# MEGA2560_Rev3e_0.net
KiCad netlist of a schematic drawn in Altium Designer
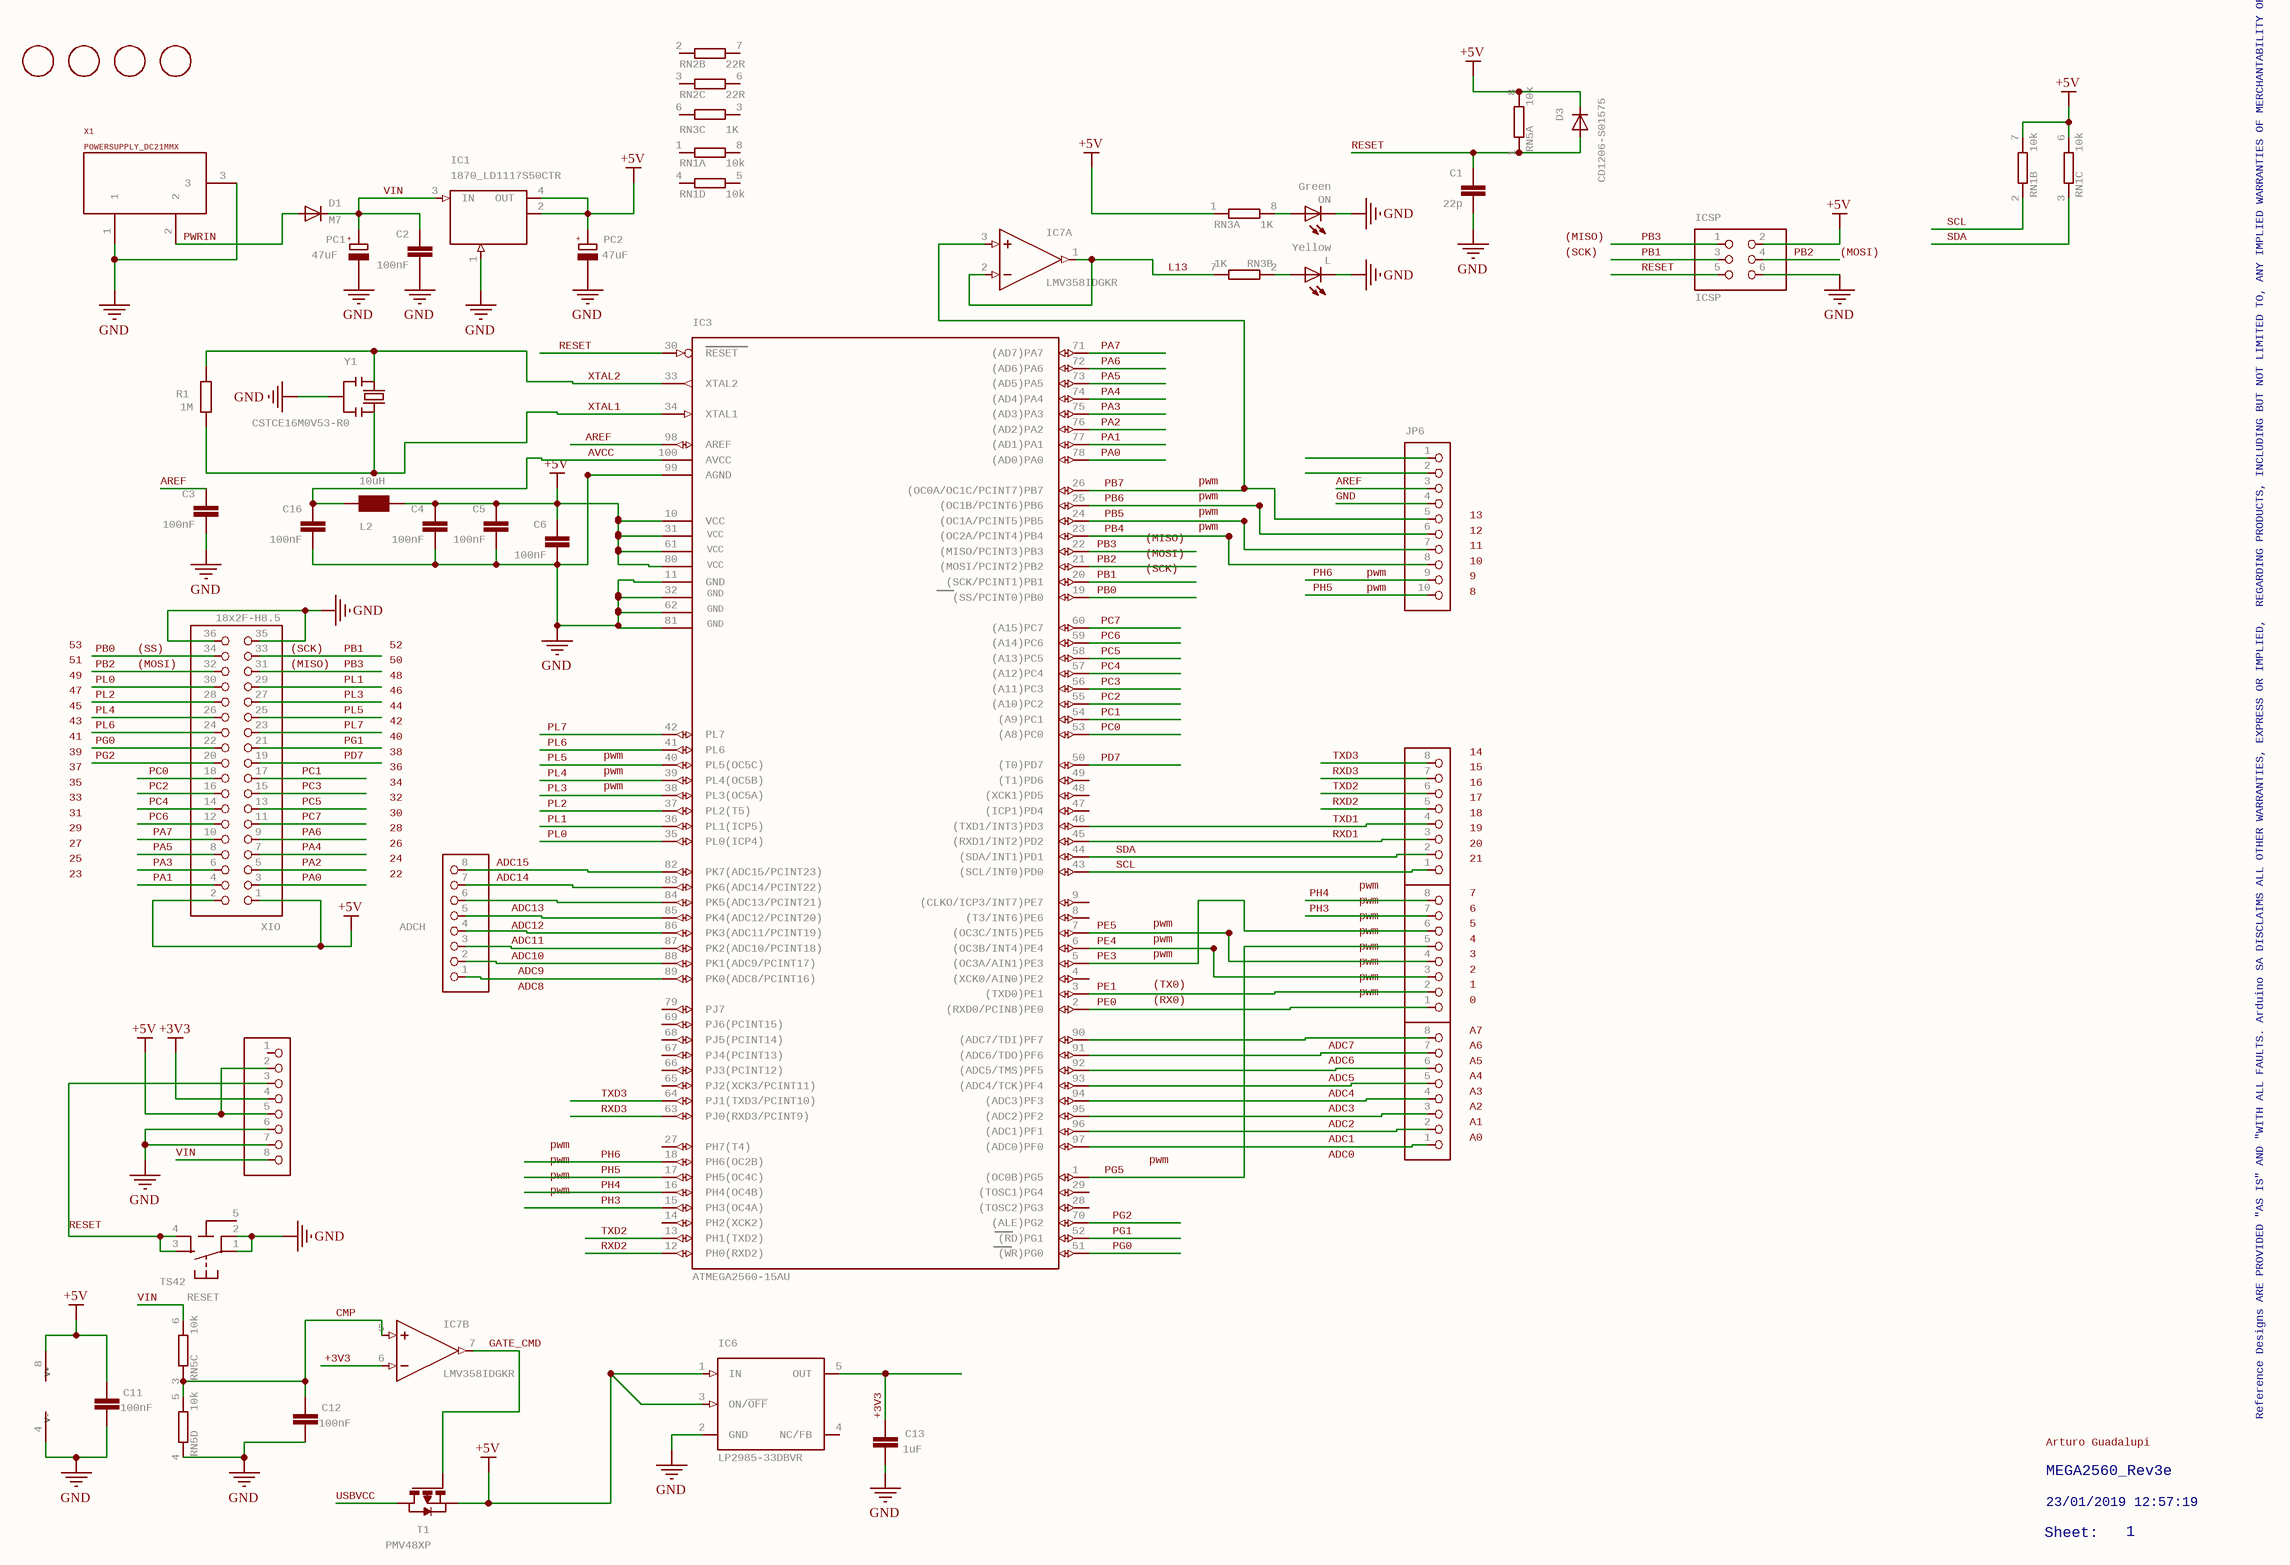
[diagram p0: MEGA2560_Rev3e_0.SchDoc]

(export (version "E")
  (design (tool "Eeschema 10.0.6"))
  (components
    (comp (ref "ADCH")
      (value "FH254-108DF08500V")
      (footprint "1X08")
      (description "Female Connector strip for Arduino bases - 8x1 F V h 8,5 p2,54mm")
      (fields (field (name "LIBRARYNAME") "Connettori"))
      (libsource (lib "Connettori") (part "0058_FH254-108DF08500V"))
    )
    (comp (ref "ADCL")
      (value "FH254-108DF08500V")
      (footprint "1X08")
      (description "Female Connector strip for Arduino bases - 8x1 F V h 8,5 p2,54mm")
      (fields (field (name "LIBRARYNAME") "Connettori"))
      (libsource (lib "Connettori") (part "0058_FH254-108DF08500V"))
    )
    (comp (ref "C1")
      (value "22p")
      (footprint "C0603-ROUND")
      (description "22pF 0603")
      (fields (field (name "PART_NUMBER") "22pF_0603"))
      (libsource (lib "Condensatori") (part "0014_22PF_0603"))
    )
    (comp (ref "C2")
      (value "100nF")
      (footprint "C0603-ROUND")
      (description "100nF 0603 50V")
      (fields (field (name "PART_NUMBER") "cl10b104kbnc"))
      (libsource (lib "Condensatori") (part "0015_100NF_0603"))
    )
    (comp (ref "C3")
      (value "100nF")
      (footprint "C0603-ROUND")
      (description "100nF 0603 50V")
      (fields (field (name "PART_NUMBER") "cl10b104kbnc"))
      (libsource (lib "Condensatori") (part "0015_100NF_0603"))
    )
    (comp (ref "C4")
      (value "100nF")
      (footprint "C0603-ROUND")
      (description "100nF 0603 50V")
      (fields (field (name "PART_NUMBER") "cl10b104kbnc"))
      (libsource (lib "Condensatori") (part "0015_100NF_0603"))
    )
    (comp (ref "C5")
      (value "100nF")
      (footprint "C0603-ROUND")
      (description "100nF 0603 50V")
      (fields (field (name "PART_NUMBER") "cl10b104kbnc"))
      (libsource (lib "Condensatori") (part "0015_100NF_0603"))
    )
    (comp (ref "C6")
      (value "100nF")
      (footprint "C0603-ROUND")
      (description "100nF 0603 50V")
      (fields (field (name "PART_NUMBER") "cl10b104kbnc"))
      (libsource (lib "Condensatori") (part "0015_100NF_0603"))
    )
    (comp (ref "C11")
      (value "100nF")
      (footprint "C0603-ROUND")
      (description "100nF 0603 50V")
      (fields (field (name "PART_NUMBER") "cl10b104kbnc"))
      (libsource (lib "") (part "0015_100NF_0603_1"))
    )
    (comp (ref "C12")
      (value "100nF")
      (footprint "C0603-ROUND")
      (description "100nF 0603 50V")
      (fields (field (name "PART_NUMBER") "cl10b104kbnc"))
      (libsource (lib "") (part "0015_100NF_0603_1"))
    )
    (comp (ref "C13")
      (value "1uF")
      (footprint "C0603-ROUND")
      (description "1uF 0603")
      (fields (field (name "PART_NUMBER") "1uF_0603/GRM188R61E105KA12D"))
      (libsource (lib "Condensatori") (part "0006_1UF_0603/GRM188R61E105KA12D"))
    )
    (comp (ref "C16")
      (value "100nF")
      (footprint "C0603-ROUND")
      (description "100nF 0603 50V")
      (fields (field (name "PART_NUMBER") "cl10b104kbnc"))
      (libsource (lib "Condensatori") (part "0015_100NF_0603"))
    )
    (comp (ref "COMMUNICATION")
      (value "FH254-108DF08500V")
      (footprint "1X08")
      (description "Female Connector strip for Arduino bases - 8x1 F V h 8,5 p2,54mm")
      (fields (field (name "LIBRARYNAME") "Connettori"))
      (libsource (lib "Connettori") (part "0058_FH254-108DF08500V"))
    )
    (comp (ref "D1")
      (value "M7")
      (footprint "SMB")
      (description "1.0A 40V SURFACE MOUNT GLASS PASSIVATED RECTIFIER   M7")
      (libsource (lib "Diodi") (part "0020_M7"))
    )
    (comp (ref "D3")
      (value "CD1206-S01575")
      (footprint "MINIMELF")
      (description "small-signal high-speed Switching Diodes   CD1206")
      (libsource (lib "Diodi") (part "0012_CD1206-S01575"))
    )
    (comp (ref "FD1")
      (value "FIDUCIALMOUNT")
      (footprint "FIDUCIA-MOUNT")
      (libsource (lib "SmartPrj") (part "FIDUCIALMOUNT"))
    )
    (comp (ref "FD2")
      (value "FIDUCIALMOUNT")
      (footprint "FIDUCIA-MOUNT")
      (libsource (lib "SmartPrj") (part "FIDUCIALMOUNT"))
    )
    (comp (ref "FD3")
      (value "FIDUCIALMOUNT")
      (footprint "FIDUCIA-MOUNT")
      (libsource (lib "SmartPrj") (part "FIDUCIALMOUNT"))
    )
    (comp (ref "FD4")
      (value "FIDUCIALMOUNT")
      (footprint "FIDUCIA-MOUNT")
      (libsource (lib "SmartPrj") (part "FIDUCIALMOUNT"))
    )
    (comp (ref "IC1")
      (value "1870_LD1117S50CTR")
      (footprint "LINEAR_SOT223")
      (description "Low-dropout linear regulator 5V  -LM1117IMPX-5.0")
      (fields (field (name "PART_NUMBER") "LD1117S50CTR"))
      (libsource (lib "IntegratedCircuits") (part "1870_LD1117S50CTR"))
    )
    (comp (ref "IC3")
      (value "ATMEGA2560-15AU")
      (footprint "TQFP100")
      (description "8-bit Microcontroller with 256K Bytes In-System Programmable Flash - ATMEGA2560-16AU")
      (fields
        (field (name "GND") "GND")
        (field (name "GND_1") "GND")
        (field (name "GND_2") "GND")
        (field (name "VCC") "VCC")
        (field (name "VCC_1") "VCC")
        (field (name "VCC_2") "VCC")
        (field (name "PART_NUMBER") "ATMEGA2560-16AU")
      )
      (libsource (lib "IntegratedCircuits") (part "0023_ATMEGA2560-16AU"))
    )
    (comp (ref "IC6")
      (value "LP2985-33DBVR")
      (footprint "SOT23-DBV")
      (description "150-mA LOW-NOISE LOW-DROPOUT REGULATOR WITH SHUTDOWN   LP2985-33DBVR")
      (fields (field (name "PART_NUMBER") "TEXLP2985-33DBVR"))
      (libsource (lib "IntegratedCircuits") (part "0008_TEXLP2985-33DBVR"))
    )
    (comp (ref "IC7")
      (value "LMV358IDGKR")
      (footprint "MSOP08")
      (fields (field (name "V+") "V+") (field (name "V-") "V-"))
      (libsource (lib "IntegratedCircuits") (part "0021_LMV358IDGKR"))
    )
    (comp (ref "ICSP")
      (value "ICSP")
      (footprint "2X03")
      (description "3x2 M V h 8,5 mm p2,54")
      (fields (field (name "PART_NUMBER") "PH254-203DF118A00V") (field (name "LIBRARYNAME") "Connettori"))
      (libsource (lib "Connettori") (part "0114_PH254-203DF118A00V"))
    )
    (comp (ref "JP6")
      (value "FH254-110DF08500V")
      (footprint "1X10")
      (description "Female Connector strip for Arduino bases - 10x1 F V h 8,5 p2,54 serigrafato STRISCIA VUOTA")
      (fields (field (name "PART_NUMBER") "FH254-110DF08500T30") (field (name "LIBRARYNAME") "Connettori"))
      (libsource (lib "Connettori") (part "1216_FH254-110DF08500T30"))
    )
    (comp (ref "L")
      (value "Yellow")
      (footprint "CHIPLED_0805")
      (description "LED YELLOW - SMD - 0805")
      (fields (field (name "PART_NUMBER") "KPT-2012YC"))
      (libsource (lib "Opto") (part "0044_KPT-2012YC"))
    )
    (comp (ref "L2")
      (value "10uH")
      (footprint "0805")
      (description "10uH 0805")
      (fields (field (name "PART_NUMBER") "CV201210-100K"))
      (libsource (lib "Induttanze") (part "0715_CV201210-100K"))
    )
    (comp (ref "ON")
      (value "Green")
      (footprint "CHIPLED_0805")
      (description "LED GREEN - SMD-0805")
      (fields (field (name "PART_NUMBER") "KPT-2012SGC"))
      (libsource (lib "Opto") (part "0043_KPT-2012SGC"))
    )
    (comp (ref "PC1")
      (value "47uF")
      (footprint "PANASONIC_D")
      (fields (field (name "+") "+"))
      (libsource (lib "Condensatori") (part "0113_47UF"))
    )
    (comp (ref "PC2")
      (value "47uF")
      (footprint "PANASONIC_D")
      (fields (field (name "+") "+"))
      (libsource (lib "Condensatori") (part "0113_47UF"))
    )
    (comp (ref "POWER")
      (value "FH254-108DF08500V")
      (footprint "1X08")
      (description "Female Connector strip for Arduino bases - 8x1 F V h 8,5 p2,54 serigrafato POWER")
      (fields (field (name "PART_NUMBER") "FH254-108DF08500T21") (field (name "LIBRARYNAME") "Connettori"))
      (libsource (lib "Connettori") (part "1217_FH254-108DF08500T21"))
    )
    (comp (ref "PWML")
      (value "FH254-108DF08500V")
      (footprint "1X08")
      (description "Female Connector strip for Arduino bases - 8x1 F V h 8,5 p2,54 serigrafato DIGITAL")
      (fields (field (name "PART_NUMBER") "FH254-108DF08500T20") (field (name "LIBRARYNAME") "Connettori"))
      (libsource (lib "Connettori") (part "1218_FH254-108DF08500T20"))
    )
    (comp (ref "R1")
      (value "1M")
      (footprint "R0603-ROUND")
      (description "1M 0603")
      (fields (field (name "PART_NUMBER") "0603_1M") (field (name "LIBRARYNAME") "Resistenze"))
      (libsource (lib "Resistenze") (part "0004_0603_1M"))
    )
    (comp (ref "RESET")
      (value "TS42")
      (footprint "TS42")
      (description "Pushbutton 6x6 Smd - White")
      (fields (field (name "PART_NUMBER") "IT-1157AHNP-160G-G_GTR"))
      (libsource (lib "Switches") (part "0946_TS42031-160W-TR-7260"))
    )
    (comp (ref "RN1")
      (value "10k")
      (footprint "CAY16")
      (description "10K 064 R")
      (fields
        (field (name "PART_NUMBER") "064R_10K_/_CAY16-103J4LF")
        (field (name "LIBRARYNAME") "Resistenze")
      )
      (libsource (lib "Resistenze") (part "0016_064R_10K_/_CAY16-103J4LF"))
    )
    (comp (ref "RN2")
      (value "22R")
      (footprint "CAY16")
      (description "22R 064R")
      (fields
        (field (name "PART_NUMBER") "064R_22R_/_CAY16-220J4LF")
        (field (name "LIBRARYNAME") "Resistenze")
      )
      (libsource (lib "Resistenze") (part "0003_064R_22R_/_CAY16-220J4LF"))
    )
    (comp (ref "RN3")
      (value "1K")
      (footprint "CAY16")
      (description "1K 064R")
      (fields
        (field (name "PART_NUMBER") "064R_1K_/_CAY16-102J4LF")
        (field (name "LIBRARYNAME") "Resistenze")
      )
      (libsource (lib "Resistenze") (part "0005_064R_1K_/_CAY16-102J4LF"))
    )
    (comp (ref "RN5")
      (value "10k")
      (footprint "CAY16")
      (description "10K 064 R")
      (fields
        (field (name "PART_NUMBER") "064R_10K_/_CAY16-103J4LF")
        (field (name "LIBRARYNAME") "Resistenze")
      )
      (libsource (lib "Resistenze") (part "0016_064R_10K_/_CAY16-103J4LF"))
    )
    (comp (ref "T1")
      (value "PMV48XP")
      (footprint "SOT-23")
      (description "20 V, 3.5 A P-channel Trench MOSFET - PMV48XP")
      (libsource (lib "Transistors") (part "0297_PMV48XP"))
    )
    (comp (ref "X1")
      (value "POWERSUPPLY_DC21MMX")
      (footprint "POWERSUPPLY_DC-21MM")
      (libsource (lib "SmartPrj") (part "POWERSUPPLY_DC21MMX"))
    )
    (comp (ref "XIO")
      (value "18x2F-H8.5")
      (footprint "2X18")
      (description "18x2 F V h 8,5 p2,54")
      (fields (field (name "PART_NUMBER") "FH254-218DF08500V") (field (name "LIBRARYNAME") "Connettori"))
      (libsource (lib "Connettori") (part "0060_FH254-218DF08500V"))
    )
    (comp (ref "Y1")
      (value "CSTCE16M0V53-R0")
      (footprint "RESONATOR")
      (description "16Mhz - SMD")
      (fields (field (name "LIBRARYNAME") "Cristalli"))
      (libsource (lib "Cristalli") (part "0011_CSTCE16M0V53-R0"))
    )
  )
  (nets
    (net (code "1") (name "+3V3") (class "Default")
      (node (ref "C13") (pin "2") (pinfunction "2_2") (pintype "passive"))
      (node (ref "IC6") (pin "5") (pinfunction "OUT_5") (pintype "passive"))
      (node (ref "IC7") (pin "6") (pinfunction "-IN_6") (pintype "input"))
      (node (ref "POWER") (pin "4") (pinfunction "4_4") (pintype "passive"))
    )
    (net (code "2") (name "+5V") (class "Default")
      (node (ref "C11") (pin "2") (pinfunction "2_2") (pintype "passive"))
      (node (ref "C4") (pin "1") (pinfunction "1_1") (pintype "passive"))
      (node (ref "C5") (pin "1") (pinfunction "1_1") (pintype "passive"))
      (node (ref "C6") (pin "1") (pinfunction "1_1") (pintype "passive"))
      (node (ref "D3") (pin "C") (pinfunction "C_C") (pintype "passive"))
      (node (ref "IC1") (pin "2") (pinfunction "OUT_2") (pintype "passive"))
      (node (ref "IC1") (pin "4") (pinfunction "OUT_4") (pintype "passive"))
      (node (ref "IC3") (pin "10") (pinfunction "VCC_10") (pintype "power_in"))
      (node (ref "IC3") (pin "31") (pinfunction "VCC1_31") (pintype "power_in"))
      (node (ref "IC3") (pin "61") (pinfunction "VCC2_61") (pintype "power_in"))
      (node (ref "IC3") (pin "80") (pinfunction "VCC3_80") (pintype "power_in"))
      (node (ref "IC6") (pin "1") (pinfunction "IN_1") (pintype "input"))
      (node (ref "IC6") (pin "3") (pinfunction "ON/~{OFF}_3") (pintype "input"))
      (node (ref "IC7") (pin "8") (pinfunction "V+_8") (pintype "power_in"))
      (node (ref "ICSP") (pin "2") (pinfunction "2_2") (pintype "passive"))
      (node (ref "L2") (pin "2") (pinfunction "2_2") (pintype "passive"))
      (node (ref "PC2") (pin "+") (pinfunction "+_+") (pintype "passive"))
      (node (ref "POWER") (pin "2") (pinfunction "2_2") (pintype "passive"))
      (node (ref "POWER") (pin "5") (pinfunction "5_5") (pintype "passive"))
      (node (ref "RN1") (pin "6") (pinfunction "2_6") (pintype "passive"))
      (node (ref "RN1") (pin "7") (pinfunction "2_7") (pintype "passive"))
      (node (ref "RN3") (pin "1") (pinfunction "1_1") (pintype "passive"))
      (node (ref "RN5") (pin "8") (pinfunction "2_8") (pintype "passive"))
      (node (ref "T1") (pin "2") (pinfunction "S_2") (pintype "passive"))
      (node (ref "XIO") (pin "1") (pinfunction "1_1") (pintype "passive"))
      (node (ref "XIO") (pin "2") (pinfunction "2_2") (pintype "passive"))
    )
    (net (code "3") (name "/ADC0") (class "Default")
      (node (ref "ADCL") (pin "1") (pinfunction "1_1") (pintype "passive"))
      (node (ref "IC3") (pin "97") (pinfunction "(ADC0)PF0_97") (pintype "bidirectional"))
    )
    (net (code "4") (name "/ADC1") (class "Default")
      (node (ref "ADCL") (pin "2") (pinfunction "2_2") (pintype "passive"))
      (node (ref "IC3") (pin "96") (pinfunction "(ADC1)PF1_96") (pintype "bidirectional"))
    )
    (net (code "5") (name "/ADC2") (class "Default")
      (node (ref "ADCL") (pin "3") (pinfunction "3_3") (pintype "passive"))
      (node (ref "IC3") (pin "95") (pinfunction "(ADC2)PF2_95") (pintype "bidirectional"))
    )
    (net (code "6") (name "/ADC3") (class "Default")
      (node (ref "ADCL") (pin "4") (pinfunction "4_4") (pintype "passive"))
      (node (ref "IC3") (pin "94") (pinfunction "(ADC3)PF3_94") (pintype "bidirectional"))
    )
    (net (code "7") (name "/ADC4") (class "Default")
      (node (ref "ADCL") (pin "5") (pinfunction "5_5") (pintype "passive"))
      (node (ref "IC3") (pin "93") (pinfunction "(ADC4/TCK)PF4_93") (pintype "bidirectional"))
    )
    (net (code "8") (name "/ADC5") (class "Default")
      (node (ref "ADCL") (pin "6") (pinfunction "6_6") (pintype "passive"))
      (node (ref "IC3") (pin "92") (pinfunction "(ADC5/TMS)PF5_92") (pintype "bidirectional"))
    )
    (net (code "9") (name "/ADC6") (class "Default")
      (node (ref "ADCL") (pin "7") (pinfunction "7_7") (pintype "passive"))
      (node (ref "IC3") (pin "91") (pinfunction "(ADC6/TDO)PF6_91") (pintype "bidirectional"))
    )
    (net (code "10") (name "/ADC7") (class "Default")
      (node (ref "ADCL") (pin "8") (pinfunction "8_8") (pintype "passive"))
      (node (ref "IC3") (pin "90") (pinfunction "(ADC7/TDI)PF7_90") (pintype "bidirectional"))
    )
    (net (code "11") (name "/ADC8") (class "Default")
      (node (ref "ADCH") (pin "1") (pinfunction "1_1") (pintype "passive"))
      (node (ref "IC3") (pin "89") (pinfunction "PK0(ADC8/PCINT16)_89") (pintype "bidirectional"))
    )
    (net (code "12") (name "/ADC9") (class "Default")
      (node (ref "ADCH") (pin "2") (pinfunction "2_2") (pintype "passive"))
      (node (ref "IC3") (pin "88") (pinfunction "PK1(ADC9/PCINT17)_88") (pintype "bidirectional"))
    )
    (net (code "13") (name "/ADC10") (class "Default")
      (node (ref "ADCH") (pin "3") (pinfunction "3_3") (pintype "passive"))
      (node (ref "IC3") (pin "87") (pinfunction "PK2(ADC10/PCINT18)_87") (pintype "bidirectional"))
    )
    (net (code "14") (name "/ADC11") (class "Default")
      (node (ref "ADCH") (pin "4") (pinfunction "4_4") (pintype "passive"))
      (node (ref "IC3") (pin "86") (pinfunction "PK3(ADC11/PCINT19)_86") (pintype "bidirectional"))
    )
    (net (code "15") (name "/ADC12") (class "Default")
      (node (ref "ADCH") (pin "5") (pinfunction "5_5") (pintype "passive"))
      (node (ref "IC3") (pin "85") (pinfunction "PK4(ADC12/PCINT20)_85") (pintype "bidirectional"))
    )
    (net (code "16") (name "/ADC13") (class "Default")
      (node (ref "ADCH") (pin "6") (pinfunction "6_6") (pintype "passive"))
      (node (ref "IC3") (pin "84") (pinfunction "PK5(ADC13/PCINT21)_84") (pintype "bidirectional"))
    )
    (net (code "17") (name "/ADC14") (class "Default")
      (node (ref "ADCH") (pin "7") (pinfunction "7_7") (pintype "passive"))
      (node (ref "IC3") (pin "83") (pinfunction "PK6(ADC14/PCINT22)_83") (pintype "bidirectional"))
    )
    (net (code "18") (name "/ADC15") (class "Default")
      (node (ref "ADCH") (pin "8") (pinfunction "8_8") (pintype "passive"))
      (node (ref "IC3") (pin "82") (pinfunction "PK7(ADC15/PCINT23)_82") (pintype "bidirectional"))
    )
    (net (code "19") (name "/AREF") (class "Default")
      (node (ref "C3") (pin "1") (pinfunction "1_1") (pintype "passive"))
      (node (ref "IC3") (pin "98") (pinfunction "AREF_98") (pintype "bidirectional"))
      (node (ref "JP6") (pin "3") (pinfunction "3_3") (pintype "passive"))
    )
    (net (code "20") (name "/AVCC") (class "Default")
      (node (ref "C16") (pin "1") (pinfunction "1_1") (pintype "passive"))
      (node (ref "IC3") (pin "100") (pinfunction "AVCC_100") (pintype "power_in"))
      (node (ref "L2") (pin "1") (pinfunction "1_1") (pintype "passive"))
    )
    (net (code "21") (name "/CMP") (class "Default")
      (node (ref "C12") (pin "2") (pinfunction "2_2") (pintype "passive"))
      (node (ref "IC7") (pin "5") (pinfunction "+IN_5") (pintype "input"))
      (node (ref "RN5") (pin "3") (pinfunction "1_3") (pintype "passive"))
      (node (ref "RN5") (pin "5") (pinfunction "2_5") (pintype "passive"))
    )
    (net (code "22") (name "/GATE_CMD") (class "Default")
      (node (ref "IC7") (pin "7") (pinfunction "OUT_7") (pintype "output"))
      (node (ref "T1") (pin "3") (pinfunction "G_3") (pintype "passive"))
    )
    (net (code "23") (name "/L13") (class "Default")
      (node (ref "IC7") (pin "1") (pinfunction "OUT_1") (pintype "output"))
      (node (ref "IC7") (pin "2") (pinfunction "-IN_2") (pintype "input"))
      (node (ref "RN3") (pin "7") (pinfunction "2_7") (pintype "passive"))
    )
    (net (code "24") (name "/PA0") (class "Default")
      (node (ref "IC3") (pin "78") (pinfunction "(AD0)PA0_78") (pintype "bidirectional"))
      (node (ref "XIO") (pin "3") (pinfunction "3_3") (pintype "passive"))
    )
    (net (code "25") (name "/PA1") (class "Default")
      (node (ref "IC3") (pin "77") (pinfunction "(AD1)PA1_77") (pintype "bidirectional"))
      (node (ref "XIO") (pin "4") (pinfunction "4_4") (pintype "passive"))
    )
    (net (code "26") (name "/PA2") (class "Default")
      (node (ref "IC3") (pin "76") (pinfunction "(AD2)PA2_76") (pintype "bidirectional"))
      (node (ref "XIO") (pin "5") (pinfunction "5_5") (pintype "passive"))
    )
    (net (code "27") (name "/PA3") (class "Default")
      (node (ref "IC3") (pin "75") (pinfunction "(AD3)PA3_75") (pintype "bidirectional"))
      (node (ref "XIO") (pin "6") (pinfunction "6_6") (pintype "passive"))
    )
    (net (code "28") (name "/PA4") (class "Default")
      (node (ref "IC3") (pin "74") (pinfunction "(AD4)PA4_74") (pintype "bidirectional"))
      (node (ref "XIO") (pin "7") (pinfunction "7_7") (pintype "passive"))
    )
    (net (code "29") (name "/PA5") (class "Default")
      (node (ref "IC3") (pin "73") (pinfunction "(AD5)PA5_73") (pintype "bidirectional"))
      (node (ref "XIO") (pin "8") (pinfunction "8_8") (pintype "passive"))
    )
    (net (code "30") (name "/PA6") (class "Default")
      (node (ref "IC3") (pin "72") (pinfunction "(AD6)PA6_72") (pintype "bidirectional"))
      (node (ref "XIO") (pin "9") (pinfunction "9_9") (pintype "passive"))
    )
    (net (code "31") (name "/PA7") (class "Default")
      (node (ref "IC3") (pin "71") (pinfunction "(AD7)PA7_71") (pintype "bidirectional"))
      (node (ref "XIO") (pin "10") (pinfunction "10_10") (pintype "passive"))
    )
    (net (code "32") (name "/PB0") (class "Default")
      (node (ref "IC3") (pin "19") (pinfunction "(SS/PCINT0)PB0_19") (pintype "bidirectional"))
      (node (ref "XIO") (pin "34") (pinfunction "34_34") (pintype "passive"))
    )
    (net (code "33") (name "/PB1") (class "Default")
      (node (ref "IC3") (pin "20") (pinfunction "(SCK/PCINT1)PB1_20") (pintype "bidirectional"))
      (node (ref "ICSP") (pin "3") (pinfunction "3_3") (pintype "passive"))
      (node (ref "XIO") (pin "33") (pinfunction "33_33") (pintype "passive"))
    )
    (net (code "34") (name "/PB2") (class "Default")
      (node (ref "IC3") (pin "21") (pinfunction "(MOSI/PCINT2)PB2_21") (pintype "bidirectional"))
      (node (ref "ICSP") (pin "4") (pinfunction "4_4") (pintype "passive"))
      (node (ref "XIO") (pin "32") (pinfunction "32_32") (pintype "passive"))
    )
    (net (code "35") (name "/PB3") (class "Default")
      (node (ref "IC3") (pin "22") (pinfunction "(MISO/PCINT3)PB3_22") (pintype "bidirectional"))
      (node (ref "ICSP") (pin "1") (pinfunction "1_1") (pintype "passive"))
      (node (ref "XIO") (pin "31") (pinfunction "31_31") (pintype "passive"))
    )
    (net (code "36") (name "/PB4") (class "Default")
      (node (ref "IC3") (pin "23") (pinfunction "(OC2A/PCINT4)PB4_23") (pintype "bidirectional"))
      (node (ref "JP6") (pin "8") (pinfunction "8_8") (pintype "passive"))
    )
    (net (code "37") (name "/PB5") (class "Default")
      (node (ref "IC3") (pin "24") (pinfunction "(OC1A/PCINT5)PB5_24") (pintype "bidirectional"))
      (node (ref "JP6") (pin "7") (pinfunction "7_7") (pintype "passive"))
    )
    (net (code "38") (name "/PB6") (class "Default")
      (node (ref "IC3") (pin "25") (pinfunction "(OC1B/PCINT6)PB6_25") (pintype "bidirectional"))
      (node (ref "JP6") (pin "6") (pinfunction "6_6") (pintype "passive"))
    )
    (net (code "39") (name "/PB7") (class "Default")
      (node (ref "IC3") (pin "26") (pinfunction "(OC0A/OC1C/PCINT7)PB7_26") (pintype "bidirectional"))
      (node (ref "IC7") (pin "3") (pinfunction "+IN_3") (pintype "input"))
      (node (ref "JP6") (pin "5") (pinfunction "5_5") (pintype "passive"))
    )
    (net (code "40") (name "/PC0") (class "Default")
      (node (ref "IC3") (pin "53") (pinfunction "(A8)PC0_53") (pintype "bidirectional"))
      (node (ref "XIO") (pin "18") (pinfunction "18_18") (pintype "passive"))
    )
    (net (code "41") (name "/PC1") (class "Default")
      (node (ref "IC3") (pin "54") (pinfunction "(A9)PC1_54") (pintype "bidirectional"))
      (node (ref "XIO") (pin "17") (pinfunction "17_17") (pintype "passive"))
    )
    (net (code "42") (name "/PC2") (class "Default")
      (node (ref "IC3") (pin "55") (pinfunction "(A10)PC2_55") (pintype "bidirectional"))
      (node (ref "XIO") (pin "16") (pinfunction "16_16") (pintype "passive"))
    )
    (net (code "43") (name "/PC3") (class "Default")
      (node (ref "IC3") (pin "56") (pinfunction "(A11)PC3_56") (pintype "bidirectional"))
      (node (ref "XIO") (pin "15") (pinfunction "15_15") (pintype "passive"))
    )
    (net (code "44") (name "/PC4") (class "Default")
      (node (ref "IC3") (pin "57") (pinfunction "(A12)PC4_57") (pintype "bidirectional"))
      (node (ref "XIO") (pin "14") (pinfunction "14_14") (pintype "passive"))
    )
    (net (code "45") (name "/PC5") (class "Default")
      (node (ref "IC3") (pin "58") (pinfunction "(A13)PC5_58") (pintype "bidirectional"))
      (node (ref "XIO") (pin "13") (pinfunction "13_13") (pintype "passive"))
    )
    (net (code "46") (name "/PC6") (class "Default")
      (node (ref "IC3") (pin "59") (pinfunction "(A14)PC6_59") (pintype "bidirectional"))
      (node (ref "XIO") (pin "12") (pinfunction "12_12") (pintype "passive"))
    )
    (net (code "47") (name "/PC7") (class "Default")
      (node (ref "IC3") (pin "60") (pinfunction "(A15)PC7_60") (pintype "bidirectional"))
      (node (ref "XIO") (pin "11") (pinfunction "11_11") (pintype "passive"))
    )
    (net (code "48") (name "/PD7") (class "Default")
      (node (ref "IC3") (pin "50") (pinfunction "(T0)PD7_50") (pintype "bidirectional"))
      (node (ref "XIO") (pin "19") (pinfunction "19_19") (pintype "passive"))
    )
    (net (code "49") (name "/PE0") (class "Default")
      (node (ref "IC3") (pin "2") (pinfunction "(RXD0/PCIN8)PE0_2") (pintype "bidirectional"))
      (node (ref "PWML") (pin "1") (pinfunction "1_1") (pintype "passive"))
    )
    (net (code "50") (name "/PE1") (class "Default")
      (node (ref "IC3") (pin "3") (pinfunction "(TXD0)PE1_3") (pintype "bidirectional"))
      (node (ref "PWML") (pin "2") (pinfunction "2_2") (pintype "passive"))
    )
    (net (code "51") (name "/PE3") (class "Default")
      (node (ref "IC3") (pin "5") (pinfunction "(OC3A/AIN1)PE3_5") (pintype "bidirectional"))
      (node (ref "PWML") (pin "6") (pinfunction "6_6") (pintype "passive"))
    )
    (net (code "52") (name "/PE4") (class "Default")
      (node (ref "IC3") (pin "6") (pinfunction "(OC3B/INT4)PE4_6") (pintype "bidirectional"))
      (node (ref "PWML") (pin "3") (pinfunction "3_3") (pintype "passive"))
    )
    (net (code "53") (name "/PE5") (class "Default")
      (node (ref "IC3") (pin "7") (pinfunction "(OC3C/INT5)PE5_7") (pintype "bidirectional"))
      (node (ref "PWML") (pin "4") (pinfunction "4_4") (pintype "passive"))
    )
    (net (code "54") (name "/PG0") (class "Default")
      (node (ref "IC3") (pin "51") (pinfunction "(WR)PG0_51") (pintype "bidirectional"))
      (node (ref "XIO") (pin "22") (pinfunction "22_22") (pintype "passive"))
    )
    (net (code "55") (name "/PG1") (class "Default")
      (node (ref "IC3") (pin "52") (pinfunction "(RD)PG1_52") (pintype "bidirectional"))
      (node (ref "XIO") (pin "21") (pinfunction "21_21") (pintype "passive"))
    )
    (net (code "56") (name "/PG2") (class "Default")
      (node (ref "IC3") (pin "70") (pinfunction "(ALE)PG2_70") (pintype "bidirectional"))
      (node (ref "XIO") (pin "20") (pinfunction "20_20") (pintype "passive"))
    )
    (net (code "57") (name "/PG5") (class "Default")
      (node (ref "IC3") (pin "1") (pinfunction "(OC0B)PG5_1") (pintype "bidirectional"))
      (node (ref "PWML") (pin "5") (pinfunction "5_5") (pintype "passive"))
    )
    (net (code "58") (name "/PH3") (class "Default")
      (node (ref "IC3") (pin "15") (pinfunction "PH3(OC4A)_15") (pintype "bidirectional"))
      (node (ref "PWML") (pin "7") (pinfunction "7_7") (pintype "passive"))
    )
    (net (code "59") (name "/PH4") (class "Default")
      (node (ref "IC3") (pin "16") (pinfunction "PH4(OC4B)_16") (pintype "bidirectional"))
      (node (ref "PWML") (pin "8") (pinfunction "8_8") (pintype "passive"))
    )
    (net (code "60") (name "/PH5") (class "Default")
      (node (ref "IC3") (pin "17") (pinfunction "PH5(OC4C)_17") (pintype "bidirectional"))
      (node (ref "JP6") (pin "10") (pinfunction "10_10") (pintype "passive"))
    )
    (net (code "61") (name "/PH6") (class "Default")
      (node (ref "IC3") (pin "18") (pinfunction "PH6(OC2B)_18") (pintype "bidirectional"))
      (node (ref "JP6") (pin "9") (pinfunction "9_9") (pintype "passive"))
    )
    (net (code "62") (name "/PL0") (class "Default")
      (node (ref "IC3") (pin "35") (pinfunction "PL0(ICP4)_35") (pintype "bidirectional"))
      (node (ref "XIO") (pin "30") (pinfunction "30_30") (pintype "passive"))
    )
    (net (code "63") (name "/PL1") (class "Default")
      (node (ref "IC3") (pin "36") (pinfunction "PL1(ICP5)_36") (pintype "bidirectional"))
      (node (ref "XIO") (pin "29") (pinfunction "29_29") (pintype "passive"))
    )
    (net (code "64") (name "/PL2") (class "Default")
      (node (ref "IC3") (pin "37") (pinfunction "PL2(T5)_37") (pintype "bidirectional"))
      (node (ref "XIO") (pin "28") (pinfunction "28_28") (pintype "passive"))
    )
    (net (code "65") (name "/PL3") (class "Default")
      (node (ref "IC3") (pin "38") (pinfunction "PL3(OC5A)_38") (pintype "bidirectional"))
      (node (ref "XIO") (pin "27") (pinfunction "27_27") (pintype "passive"))
    )
    (net (code "66") (name "/PL4") (class "Default")
      (node (ref "IC3") (pin "39") (pinfunction "PL4(OC5B)_39") (pintype "bidirectional"))
      (node (ref "XIO") (pin "26") (pinfunction "26_26") (pintype "passive"))
    )
    (net (code "67") (name "/PL5") (class "Default")
      (node (ref "IC3") (pin "40") (pinfunction "PL5(OC5C)_40") (pintype "bidirectional"))
      (node (ref "XIO") (pin "25") (pinfunction "25_25") (pintype "passive"))
    )
    (net (code "68") (name "/PL6") (class "Default")
      (node (ref "IC3") (pin "41") (pinfunction "PL6_41") (pintype "bidirectional"))
      (node (ref "XIO") (pin "24") (pinfunction "24_24") (pintype "passive"))
    )
    (net (code "69") (name "/PL7") (class "Default")
      (node (ref "IC3") (pin "42") (pinfunction "PL7_42") (pintype "bidirectional"))
      (node (ref "XIO") (pin "23") (pinfunction "23_23") (pintype "passive"))
    )
    (net (code "70") (name "/PWRIN") (class "Default")
      (node (ref "D1") (pin "A") (pinfunction "A_A") (pintype "passive"))
      (node (ref "X1") (pin "2") (pinfunction "2_2") (pintype "power_in"))
    )
    (net (code "71") (name "/RESET") (class "Default")
      (node (ref "C1") (pin "1") (pinfunction "1_1") (pintype "passive"))
      (node (ref "D3") (pin "A") (pinfunction "A_A") (pintype "passive"))
      (node (ref "IC3") (pin "30") (pinfunction "RESET_30") (pintype "input"))
      (node (ref "ICSP") (pin "5") (pinfunction "5_5") (pintype "passive"))
      (node (ref "POWER") (pin "3") (pinfunction "3_3") (pintype "passive"))
      (node (ref "RESET") (pin "3") (pinfunction "3_3") (pintype "passive"))
      (node (ref "RESET") (pin "4") (pinfunction "4_4") (pintype "passive"))
      (node (ref "RN5") (pin "1") (pinfunction "1_1") (pintype "passive"))
    )
    (net (code "72") (name "/RXD1") (class "Default")
      (node (ref "COMMUNICATION") (pin "3") (pinfunction "3_3") (pintype "passive"))
      (node (ref "IC3") (pin "45") (pinfunction "(RXD1/INT2)PD2_45") (pintype "bidirectional"))
    )
    (net (code "73") (name "/RXD2") (class "Default")
      (node (ref "COMMUNICATION") (pin "5") (pinfunction "5_5") (pintype "passive"))
      (node (ref "IC3") (pin "12") (pinfunction "PH0(RXD2)_12") (pintype "bidirectional"))
    )
    (net (code "74") (name "/RXD3") (class "Default")
      (node (ref "COMMUNICATION") (pin "7") (pinfunction "7_7") (pintype "passive"))
      (node (ref "IC3") (pin "63") (pinfunction "PJ0(RXD3/PCINT9)_63") (pintype "bidirectional"))
    )
    (net (code "75") (name "/SCL") (class "Default")
      (node (ref "COMMUNICATION") (pin "1") (pinfunction "1_1") (pintype "passive"))
      (node (ref "IC3") (pin "43") (pinfunction "(SCL/INT0)PD0_43") (pintype "bidirectional"))
      (node (ref "RN1") (pin "2") (pinfunction "1_2") (pintype "passive"))
    )
    (net (code "76") (name "/SDA") (class "Default")
      (node (ref "COMMUNICATION") (pin "2") (pinfunction "2_2") (pintype "passive"))
      (node (ref "IC3") (pin "44") (pinfunction "(SDA/INT1)PD1_44") (pintype "bidirectional"))
      (node (ref "RN1") (pin "3") (pinfunction "1_3") (pintype "passive"))
    )
    (net (code "77") (name "/TXD1") (class "Default")
      (node (ref "COMMUNICATION") (pin "4") (pinfunction "4_4") (pintype "passive"))
      (node (ref "IC3") (pin "46") (pinfunction "(TXD1/INT3)PD3_46") (pintype "bidirectional"))
    )
    (net (code "78") (name "/TXD2") (class "Default")
      (node (ref "COMMUNICATION") (pin "6") (pinfunction "6_6") (pintype "passive"))
      (node (ref "IC3") (pin "13") (pinfunction "PH1(TXD2)_13") (pintype "bidirectional"))
    )
    (net (code "79") (name "/TXD3") (class "Default")
      (node (ref "COMMUNICATION") (pin "8") (pinfunction "8_8") (pintype "passive"))
      (node (ref "IC3") (pin "64") (pinfunction "PJ1(TXD3/PCINT10)_64") (pintype "bidirectional"))
    )
    (net (code "80") (name "/USBVCC") (class "Default")
      (node (ref "T1") (pin "1") (pinfunction "D_1") (pintype "passive"))
    )
    (net (code "81") (name "/VIN") (class "Default")
      (node (ref "C2") (pin "1") (pinfunction "1_1") (pintype "passive"))
      (node (ref "D1") (pin "C") (pinfunction "C_C") (pintype "passive"))
      (node (ref "IC1") (pin "3") (pinfunction "IN_3") (pintype "input"))
      (node (ref "PC1") (pin "+") (pinfunction "+_+") (pintype "passive"))
      (node (ref "POWER") (pin "8") (pinfunction "8_8") (pintype "passive"))
      (node (ref "RN5") (pin "6") (pinfunction "2_6") (pintype "passive"))
    )
    (net (code "82") (name "/XTAL1") (class "Default")
      (node (ref "IC3") (pin "34") (pinfunction "XTAL1_34") (pintype "input"))
      (node (ref "R1") (pin "1") (pinfunction "1_1") (pintype "passive"))
      (node (ref "Y1") (pin "3") (pinfunction "3_3") (pintype "passive"))
    )
    (net (code "83") (name "/XTAL2") (class "Default")
      (node (ref "IC3") (pin "33") (pinfunction "XTAL2_33") (pintype "output"))
      (node (ref "R1") (pin "2") (pinfunction "2_2") (pintype "passive"))
      (node (ref "Y1") (pin "1") (pinfunction "1_1") (pintype "passive"))
    )
    (net (code "84") (name "GND") (class "Default")
      (node (ref "C1") (pin "2") (pinfunction "2_2") (pintype "passive"))
      (node (ref "C11") (pin "1") (pinfunction "1_1") (pintype "passive"))
      (node (ref "C12") (pin "1") (pinfunction "1_1") (pintype "passive"))
      (node (ref "C13") (pin "1") (pinfunction "1_1") (pintype "passive"))
      (node (ref "C16") (pin "2") (pinfunction "2_2") (pintype "passive"))
      (node (ref "C2") (pin "2") (pinfunction "2_2") (pintype "passive"))
      (node (ref "C3") (pin "2") (pinfunction "2_2") (pintype "passive"))
      (node (ref "C4") (pin "2") (pinfunction "2_2") (pintype "passive"))
      (node (ref "C5") (pin "2") (pinfunction "2_2") (pintype "passive"))
      (node (ref "C6") (pin "2") (pinfunction "2_2") (pintype "passive"))
      (node (ref "IC1") (pin "1") (pinfunction "GND/ADJ_1") (pintype "input"))
      (node (ref "IC3") (pin "11") (pinfunction "GND_11") (pintype "power_in"))
      (node (ref "IC3") (pin "32") (pinfunction "GND1_32") (pintype "power_in"))
      (node (ref "IC3") (pin "62") (pinfunction "GND2_62") (pintype "power_in"))
      (node (ref "IC3") (pin "81") (pinfunction "GND3_81") (pintype "power_in"))
      (node (ref "IC3") (pin "99") (pinfunction "AGND_99") (pintype "power_in"))
      (node (ref "IC6") (pin "2") (pinfunction "GND_2") (pintype "power_in"))
      (node (ref "IC7") (pin "4") (pinfunction "V-_4") (pintype "power_in"))
      (node (ref "ICSP") (pin "6") (pinfunction "6_6") (pintype "passive"))
      (node (ref "JP6") (pin "4") (pinfunction "4_4") (pintype "passive"))
      (node (ref "L") (pin "C") (pinfunction "C_C") (pintype "passive"))
      (node (ref "ON") (pin "C") (pinfunction "C_C") (pintype "passive"))
      (node (ref "PC1") (pin "-") (pinfunction "-_-") (pintype "passive"))
      (node (ref "PC2") (pin "-") (pinfunction "-_-") (pintype "passive"))
      (node (ref "POWER") (pin "6") (pinfunction "6_6") (pintype "passive"))
      (node (ref "POWER") (pin "7") (pinfunction "7_7") (pintype "passive"))
      (node (ref "RESET") (pin "1") (pinfunction "1_1") (pintype "passive"))
      (node (ref "RESET") (pin "2") (pinfunction "2_2") (pintype "passive"))
      (node (ref "RN5") (pin "4") (pinfunction "1_4") (pintype "passive"))
      (node (ref "X1") (pin "1") (pinfunction "1_1") (pintype "power_in"))
      (node (ref "X1") (pin "3") (pinfunction "3_3") (pintype "power_in"))
      (node (ref "XIO") (pin "35") (pinfunction "35_35") (pintype "passive"))
      (node (ref "XIO") (pin "36") (pinfunction "36_36") (pintype "passive"))
      (node (ref "Y1") (pin "2") (pinfunction "2_2") (pintype "passive"))
    )
    (net (code "85") (name "Net-(RN3A-2)") (class "Default")
      (node (ref "ON") (pin "A") (pinfunction "A_A") (pintype "passive"))
      (node (ref "RN3") (pin "8") (pinfunction "2_8") (pintype "passive"))
    )
    (net (code "86") (name "Net-(RN3B-1)") (class "Default")
      (node (ref "L") (pin "A") (pinfunction "A_A") (pintype "passive"))
      (node (ref "RN3") (pin "2") (pinfunction "1_2") (pintype "passive"))
    )
    (net (code "87") (name "unconnected-(IC3-(CLKO{slash}ICP3{slash}INT7)PE7-Pad9)") (class "Default")
      (node (ref "IC3") (pin "9") (pinfunction "(CLKO/ICP3/INT7)PE7_9") (pintype "bidirectional"))
    )
    (net (code "88") (name "unconnected-(IC3-(ICP1)PD4-Pad47)") (class "Default")
      (node (ref "IC3") (pin "47") (pinfunction "(ICP1)PD4_47") (pintype "bidirectional"))
    )
    (net (code "89") (name "unconnected-(IC3-(T1)PD6-Pad49)") (class "Default")
      (node (ref "IC3") (pin "49") (pinfunction "(T1)PD6_49") (pintype "bidirectional"))
    )
    (net (code "90") (name "unconnected-(IC3-(T3{slash}INT6)PE6-Pad8)") (class "Default")
      (node (ref "IC3") (pin "8") (pinfunction "(T3/INT6)PE6_8") (pintype "bidirectional"))
    )
    (net (code "91") (name "unconnected-(IC3-(TOSC1)PG4-Pad29)") (class "Default")
      (node (ref "IC3") (pin "29") (pinfunction "(TOSC1)PG4_29") (pintype "bidirectional"))
    )
    (net (code "92") (name "unconnected-(IC3-(TOSC2)PG3-Pad28)") (class "Default")
      (node (ref "IC3") (pin "28") (pinfunction "(TOSC2)PG3_28") (pintype "bidirectional"))
    )
    (net (code "93") (name "unconnected-(IC3-(XCK0{slash}AIN0)PE2-Pad4)") (class "Default")
      (node (ref "IC3") (pin "4") (pinfunction "(XCK0/AIN0)PE2_4") (pintype "bidirectional"))
    )
    (net (code "94") (name "unconnected-(IC3-(XCK1)PD5-Pad48)") (class "Default")
      (node (ref "IC3") (pin "48") (pinfunction "(XCK1)PD5_48") (pintype "bidirectional"))
    )
    (net (code "95") (name "unconnected-(IC3-PH2(XCK2)-Pad14)") (class "Default")
      (node (ref "IC3") (pin "14") (pinfunction "PH2(XCK2)_14") (pintype "bidirectional"))
    )
    (net (code "96") (name "unconnected-(IC3-PH7(T4)-Pad27)") (class "Default")
      (node (ref "IC3") (pin "27") (pinfunction "PH7(T4)_27") (pintype "bidirectional"))
    )
    (net (code "97") (name "unconnected-(IC3-PJ2(XCK3{slash}PCINT11)-Pad65)") (class "Default")
      (node (ref "IC3") (pin "65") (pinfunction "PJ2(XCK3/PCINT11)_65") (pintype "bidirectional"))
    )
    (net (code "98") (name "unconnected-(IC3-PJ3(PCINT12)-Pad66)") (class "Default")
      (node (ref "IC3") (pin "66") (pinfunction "PJ3(PCINT12)_66") (pintype "bidirectional"))
    )
    (net (code "99") (name "unconnected-(IC3-PJ4(PCINT13)-Pad67)") (class "Default")
      (node (ref "IC3") (pin "67") (pinfunction "PJ4(PCINT13)_67") (pintype "bidirectional"))
    )
    (net (code "100") (name "unconnected-(IC3-PJ5(PCINT14)-Pad68)") (class "Default")
      (node (ref "IC3") (pin "68") (pinfunction "PJ5(PCINT14)_68") (pintype "bidirectional"))
    )
    (net (code "101") (name "unconnected-(IC3-PJ6(PCINT15)-Pad69)") (class "Default")
      (node (ref "IC3") (pin "69") (pinfunction "PJ6(PCINT15)_69") (pintype "bidirectional"))
    )
    (net (code "102") (name "unconnected-(IC3-PJ7-Pad79)") (class "Default")
      (node (ref "IC3") (pin "79") (pinfunction "PJ7_79") (pintype "bidirectional"))
    )
    (net (code "103") (name "unconnected-(IC6-NC{slash}FB-Pad4)") (class "Default")
      (node (ref "IC6") (pin "4") (pinfunction "NC/FB_4") (pintype "passive"))
    )
    (net (code "104") (name "unconnected-(JP6-Pad1)") (class "Default")
      (node (ref "JP6") (pin "1") (pinfunction "1_1") (pintype "passive"))
    )
    (net (code "105") (name "unconnected-(JP6-Pad2)") (class "Default")
      (node (ref "JP6") (pin "2") (pinfunction "2_2") (pintype "passive"))
    )
    (net (code "106") (name "unconnected-(POWER-Pad1)") (class "Default")
      (node (ref "POWER") (pin "1") (pinfunction "1_1") (pintype "passive"))
    )
    (net (code "107") (name "unconnected-(RESET-5-GND-Pad5)") (class "Default")
      (node (ref "RESET") (pin "5") (pinfunction "5-GND_5") (pintype "power_in"))
    )
    (net (code "108") (name "unconnected-(RN1-Pad1)") (class "Default")
      (node (ref "RN1") (pin "1") (pinfunction "1_1") (pintype "passive"))
    )
    (net (code "109") (name "unconnected-(RN1A-2-Pad8)") (class "Default")
      (node (ref "RN1") (pin "8") (pinfunction "2_8") (pintype "passive"))
    )
    (net (code "110") (name "unconnected-(RN1D-1-Pad4)") (class "Default")
      (node (ref "RN1") (pin "4") (pinfunction "1_4") (pintype "passive"))
    )
    (net (code "111") (name "unconnected-(RN1D-2-Pad5)") (class "Default")
      (node (ref "RN1") (pin "5") (pinfunction "2_5") (pintype "passive"))
    )
    (net (code "112") (name "unconnected-(RN2B-1-Pad2)") (class "Default")
      (node (ref "RN2") (pin "2") (pinfunction "1_2") (pintype "passive"))
    )
    (net (code "113") (name "unconnected-(RN2B-2-Pad7)") (class "Default")
      (node (ref "RN2") (pin "7") (pinfunction "2_7") (pintype "passive"))
    )
    (net (code "114") (name "unconnected-(RN2C-1-Pad3)") (class "Default")
      (node (ref "RN2") (pin "3") (pinfunction "1_3") (pintype "passive"))
    )
    (net (code "115") (name "unconnected-(RN2C-2-Pad6)") (class "Default")
      (node (ref "RN2") (pin "6") (pinfunction "2_6") (pintype "passive"))
    )
    (net (code "116") (name "unconnected-(RN3C-1-Pad3)") (class "Default")
      (node (ref "RN3") (pin "3") (pinfunction "1_3") (pintype "passive"))
    )
    (net (code "117") (name "unconnected-(RN3C-2-Pad6)") (class "Default")
      (node (ref "RN3") (pin "6") (pinfunction "2_6") (pintype "passive"))
    )
  )
)
